# DAC7731.net
KiCad netlist of a schematic drawn in Altium Designer
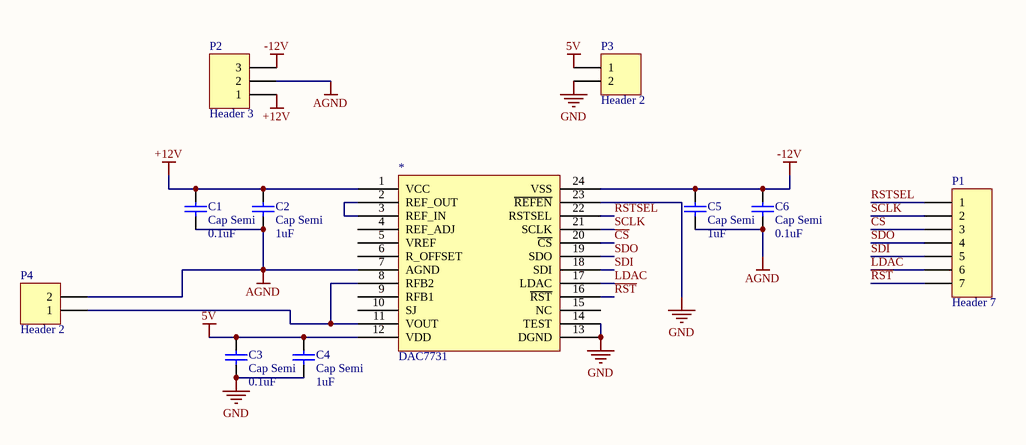
[diagram p0: DAC7731.SchDoc]

(export (version "E")
  (design (tool "Eeschema 10.0.6"))
  (components
    (comp (ref "*")
      (value "DAC7731")
      (footprint "TSSOP24")
      (libsource (lib "DAC7731Schlib") (part "DAC7731"))
    )
    (comp (ref "C1")
      (value "Cap Semi")
      (footprint "C1206")
      (description "Capacitor (Semiconductor SIM Model)")
      (fields (field (name "ALTIUM_VALUE") "0.1uF") (field (name "PUBLISHER") "Altium Limited"))
      (libsource (lib "Miscellaneous Devices") (part "Cap Semi"))
    )
    (comp (ref "C2")
      (value "Cap Semi")
      (footprint "C1206")
      (description "Capacitor (Semiconductor SIM Model)")
      (fields (field (name "ALTIUM_VALUE") "1uF") (field (name "PUBLISHER") "Altium Limited"))
      (libsource (lib "Miscellaneous Devices") (part "Cap Semi"))
    )
    (comp (ref "C3")
      (value "Cap Semi")
      (footprint "C1206")
      (description "Capacitor (Semiconductor SIM Model)")
      (fields (field (name "ALTIUM_VALUE") "0.1uF") (field (name "PUBLISHER") "Altium Limited"))
      (libsource (lib "Miscellaneous Devices") (part "Cap Semi"))
    )
    (comp (ref "C4")
      (value "Cap Semi")
      (footprint "C1206")
      (description "Capacitor (Semiconductor SIM Model)")
      (fields (field (name "ALTIUM_VALUE") "1uF") (field (name "PUBLISHER") "Altium Limited"))
      (libsource (lib "Miscellaneous Devices") (part "Cap Semi"))
    )
    (comp (ref "C5")
      (value "Cap Semi")
      (footprint "C1206")
      (description "Capacitor (Semiconductor SIM Model)")
      (fields (field (name "ALTIUM_VALUE") "1uF") (field (name "PUBLISHER") "Altium Limited"))
      (libsource (lib "Miscellaneous Devices") (part "Cap Semi"))
    )
    (comp (ref "C6")
      (value "Cap Semi")
      (footprint "C1206")
      (description "Capacitor (Semiconductor SIM Model)")
      (fields (field (name "ALTIUM_VALUE") "0.1uF") (field (name "PUBLISHER") "Altium Limited"))
      (libsource (lib "Miscellaneous Devices") (part "Cap Semi"))
    )
    (comp (ref "P1")
      (value "Header 7")
      (footprint "HDR1X7")
      (description "Header, 7-Pin")
      (fields (field (name "PUBLISHER") "Altium Limited"))
      (libsource (lib "Miscellaneous Connectors") (part "Header 7"))
    )
    (comp (ref "P2")
      (value "Header 3")
      (footprint "HDR1X3")
      (description "Header, 3-Pin")
      (fields (field (name "PUBLISHER") "Altium Limited"))
      (libsource (lib "Miscellaneous Connectors") (part "Header 3"))
    )
    (comp (ref "P3")
      (value "Header 2")
      (footprint "HDR1X2")
      (description "Header, 2-Pin")
      (fields (field (name "PUBLISHER") "Altium Limited"))
      (libsource (lib "Miscellaneous Connectors") (part "Header 2"))
    )
    (comp (ref "P4")
      (value "Header 2")
      (footprint "HDR1X2")
      (description "Header, 2-Pin")
      (fields (field (name "PUBLISHER") "Altium Limited"))
      (libsource (lib "") (part "Header 2_1"))
    )
  )
  (nets
    (net (code "1") (name "+12V") (class "Default")
      (node (ref "*") (pin "1") (pinfunction "VCC_1") (pintype "passive"))
      (node (ref "C1") (pin "2") (pinfunction "2_2") (pintype "passive"))
      (node (ref "C2") (pin "2") (pinfunction "2_2") (pintype "passive"))
      (node (ref "P2") (pin "1") (pinfunction "1_1") (pintype "passive"))
    )
    (net (code "2") (name "-12V") (class "Default")
      (node (ref "*") (pin "24") (pinfunction "VSS_24") (pintype "passive"))
      (node (ref "C5") (pin "2") (pinfunction "2_2") (pintype "passive"))
      (node (ref "C6") (pin "2") (pinfunction "2_2") (pintype "passive"))
      (node (ref "P2") (pin "3") (pinfunction "3_3") (pintype "passive"))
    )
    (net (code "3") (name "/LDAC") (class "Default")
      (node (ref "*") (pin "17") (pinfunction "LDAC_17") (pintype "passive"))
      (node (ref "P1") (pin "6") (pinfunction "6_6") (pintype "passive"))
    )
    (net (code "4") (name "/RSTSEL") (class "Default")
      (node (ref "*") (pin "22") (pinfunction "RSTSEL_22") (pintype "passive"))
      (node (ref "P1") (pin "1") (pinfunction "1_1") (pintype "passive"))
    )
    (net (code "5") (name "/SCLK") (class "Default")
      (node (ref "*") (pin "21") (pinfunction "SCLK_21") (pintype "passive"))
      (node (ref "P1") (pin "2") (pinfunction "2_2") (pintype "passive"))
    )
    (net (code "6") (name "/SDI") (class "Default")
      (node (ref "*") (pin "18") (pinfunction "SDI_18") (pintype "passive"))
      (node (ref "P1") (pin "5") (pinfunction "5_5") (pintype "passive"))
    )
    (net (code "7") (name "/SDO") (class "Default")
      (node (ref "*") (pin "19") (pinfunction "SDO_19") (pintype "passive"))
      (node (ref "P1") (pin "4") (pinfunction "4_4") (pintype "passive"))
    )
    (net (code "8") (name "/~{CS}") (class "Default")
      (node (ref "*") (pin "20") (pinfunction "~{CS}_20") (pintype "passive"))
      (node (ref "P1") (pin "3") (pinfunction "3_3") (pintype "passive"))
    )
    (net (code "9") (name "/~{RST}") (class "Default")
      (node (ref "*") (pin "16") (pinfunction "~{RST}_16") (pintype "passive"))
      (node (ref "P1") (pin "7") (pinfunction "7_7") (pintype "passive"))
    )
    (net (code "10") (name "5V") (class "Default")
      (node (ref "*") (pin "12") (pinfunction "VDD_12") (pintype "passive"))
      (node (ref "C3") (pin "2") (pinfunction "2_2") (pintype "passive"))
      (node (ref "C4") (pin "2") (pinfunction "2_2") (pintype "passive"))
      (node (ref "P3") (pin "1") (pinfunction "1_1") (pintype "passive"))
    )
    (net (code "11") (name "AGND") (class "Default")
      (node (ref "*") (pin "7") (pinfunction "AGND_7") (pintype "passive"))
      (node (ref "C1") (pin "1") (pinfunction "1_1") (pintype "passive"))
      (node (ref "C2") (pin "1") (pinfunction "1_1") (pintype "passive"))
      (node (ref "C5") (pin "1") (pinfunction "1_1") (pintype "passive"))
      (node (ref "C6") (pin "1") (pinfunction "1_1") (pintype "passive"))
      (node (ref "P2") (pin "2") (pinfunction "2_2") (pintype "passive"))
      (node (ref "P4") (pin "2") (pinfunction "2_2") (pintype "passive"))
    )
    (net (code "12") (name "GND") (class "Default")
      (node (ref "*") (pin "13") (pinfunction "DGND_13") (pintype "passive"))
      (node (ref "*") (pin "14") (pinfunction "TEST_14") (pintype "passive"))
      (node (ref "*") (pin "23") (pinfunction "~{REFEN}_23") (pintype "passive"))
      (node (ref "C3") (pin "1") (pinfunction "1_1") (pintype "passive"))
      (node (ref "C4") (pin "1") (pinfunction "1_1") (pintype "passive"))
      (node (ref "P3") (pin "2") (pinfunction "2_2") (pintype "passive"))
    )
    (net (code "13") (name "Net-(*-REF_IN)") (class "Default")
      (node (ref "*") (pin "2") (pinfunction "REF_OUT_2") (pintype "passive"))
      (node (ref "*") (pin "3") (pinfunction "REF_IN_3") (pintype "passive"))
    )
    (net (code "14") (name "Net-(*-RFB2)") (class "Default")
      (node (ref "*") (pin "11") (pinfunction "VOUT_11") (pintype "passive"))
      (node (ref "*") (pin "8") (pinfunction "RFB2_8") (pintype "passive"))
      (node (ref "P4") (pin "1") (pinfunction "1_1") (pintype "passive"))
    )
    (net (code "15") (name "unconnected-(*-NC-Pad15)") (class "Default")
      (node (ref "*") (pin "15") (pinfunction "NC_15") (pintype "passive"))
    )
    (net (code "16") (name "unconnected-(*-REF_ADJ-Pad4)") (class "Default")
      (node (ref "*") (pin "4") (pinfunction "REF_ADJ_4") (pintype "passive"))
    )
    (net (code "17") (name "unconnected-(*-RFB1-Pad9)") (class "Default")
      (node (ref "*") (pin "9") (pinfunction "RFB1_9") (pintype "passive"))
    )
    (net (code "18") (name "unconnected-(*-R_OFFSET-Pad6)") (class "Default")
      (node (ref "*") (pin "6") (pinfunction "R_OFFSET_6") (pintype "passive"))
    )
    (net (code "19") (name "unconnected-(*-SJ-Pad10)") (class "Default")
      (node (ref "*") (pin "10") (pinfunction "SJ_10") (pintype "passive"))
    )
    (net (code "20") (name "unconnected-(*-VREF-Pad5)") (class "Default")
      (node (ref "*") (pin "5") (pinfunction "VREF_5") (pintype "passive"))
    )
  )
)
